# lighting_sign.net
KiCad netlist of a schematic drawn in EAGLE
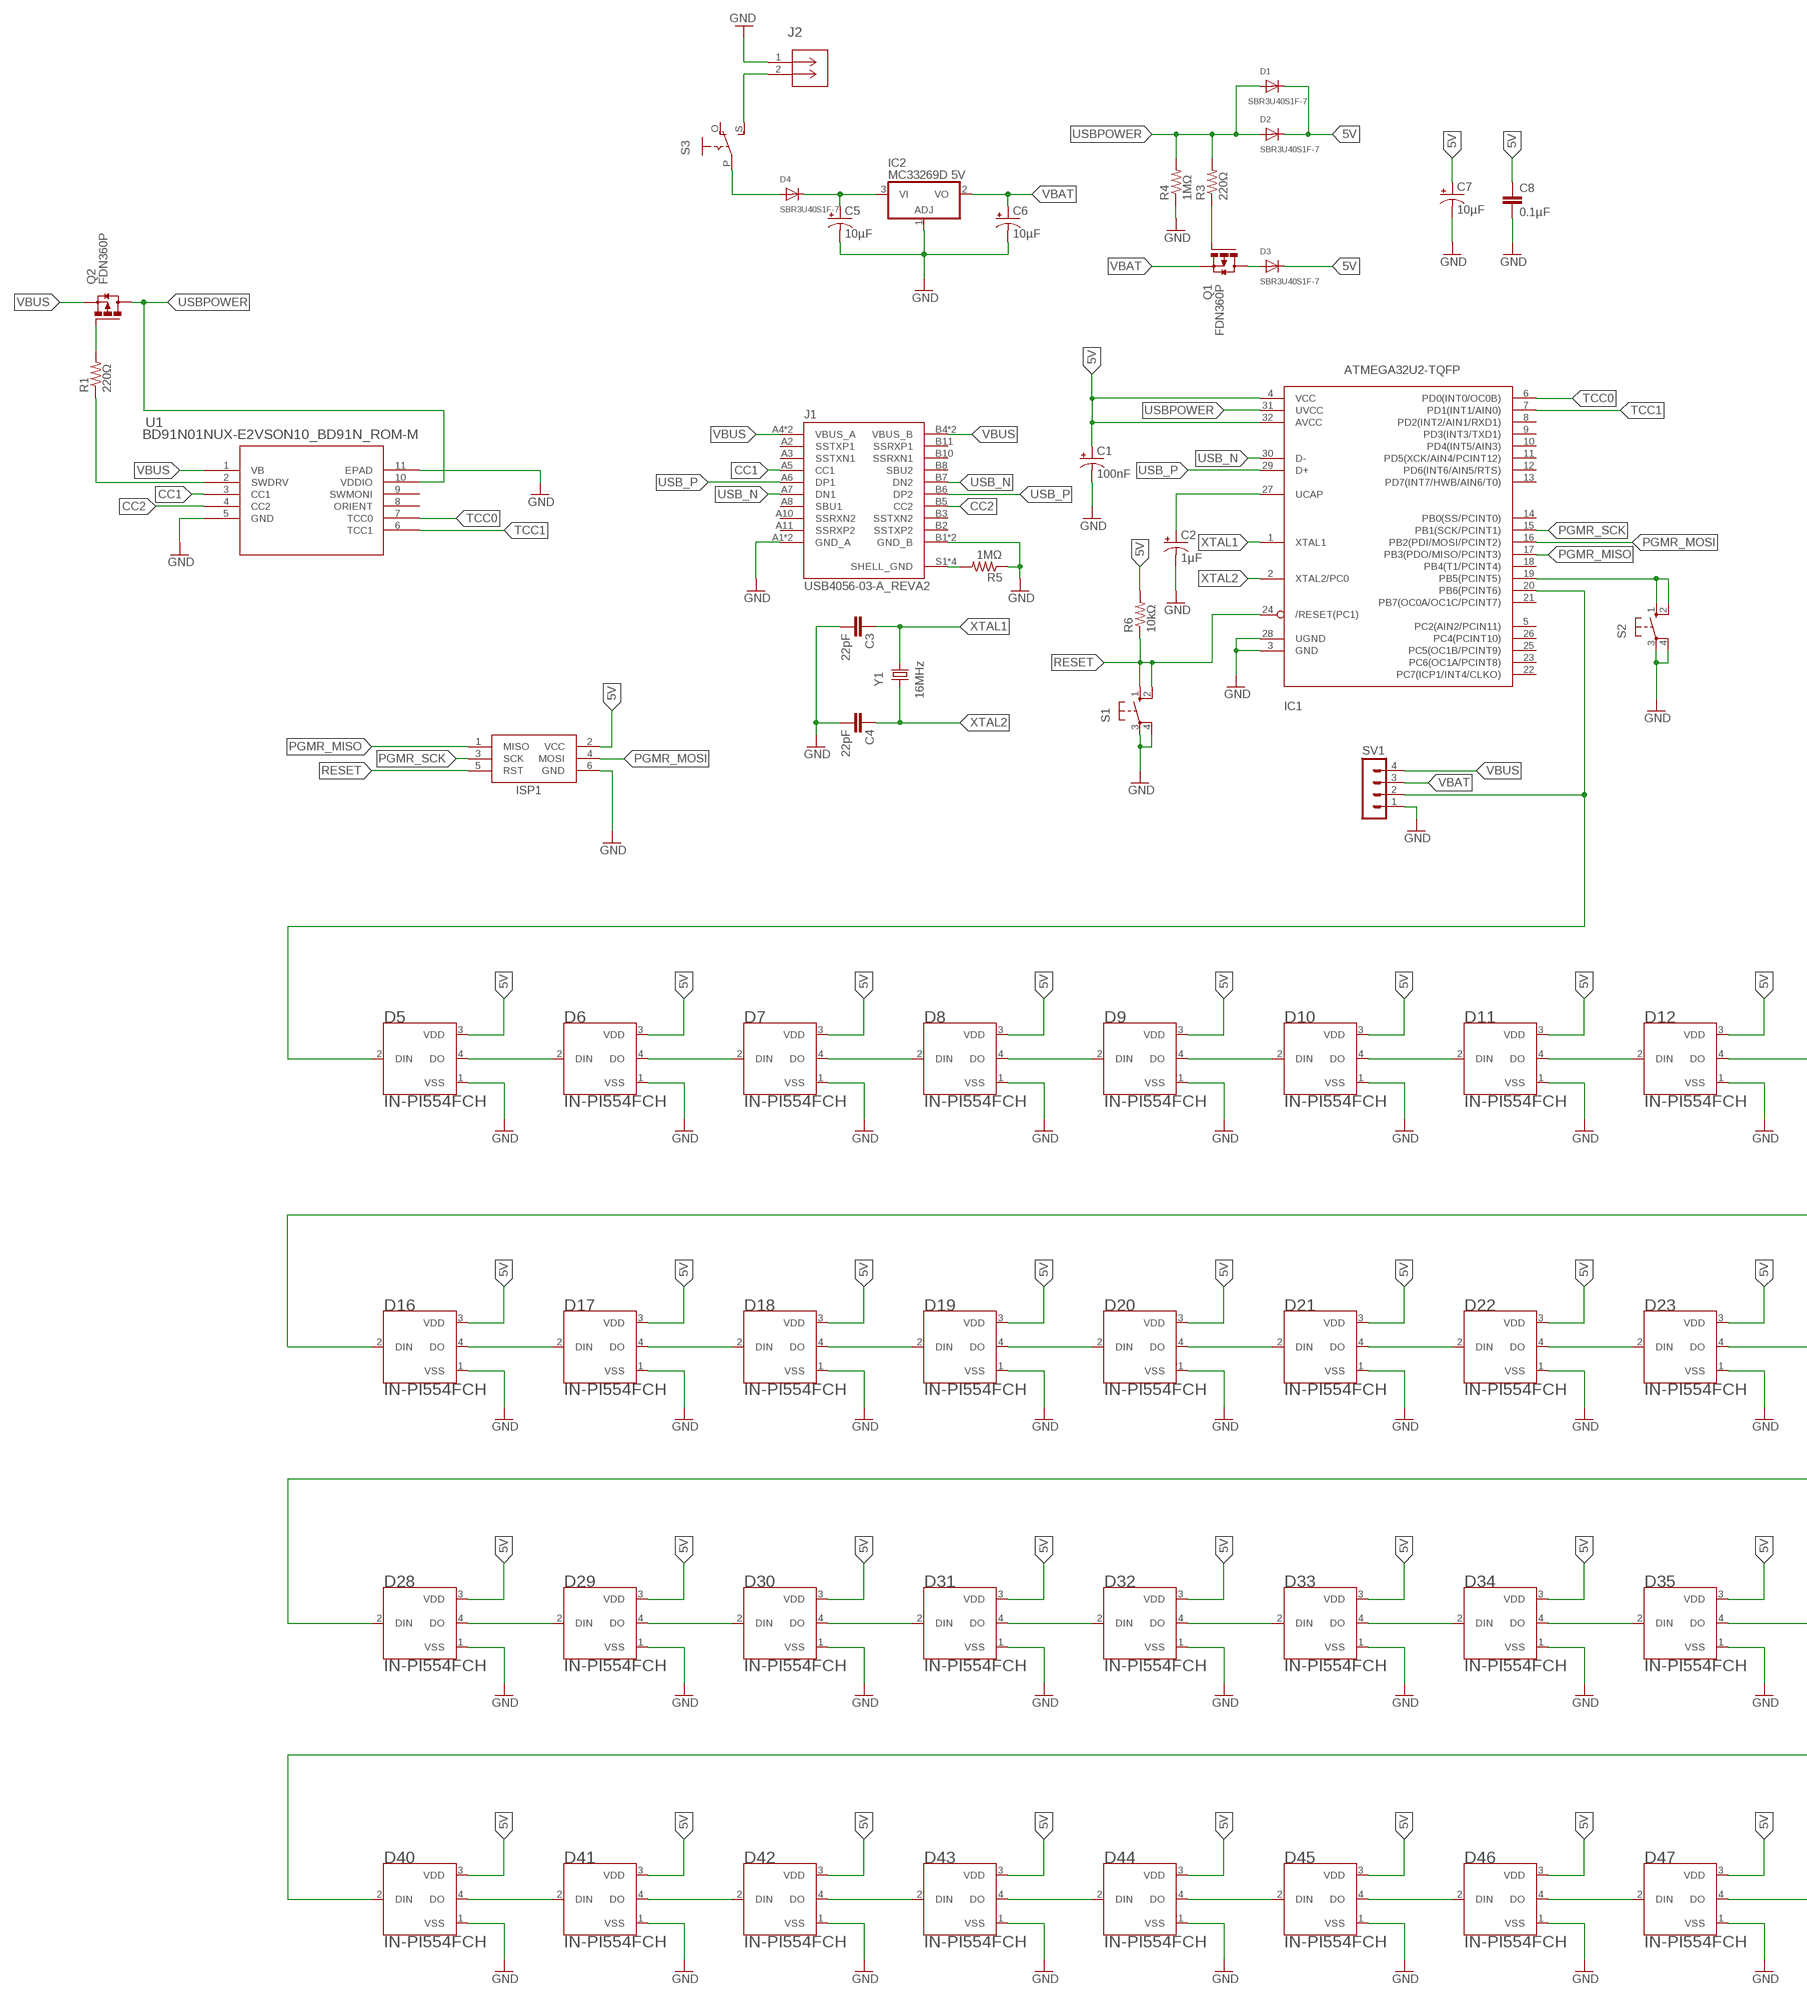
[diagram p0: schematic, sheet 1, part 1 of 2]
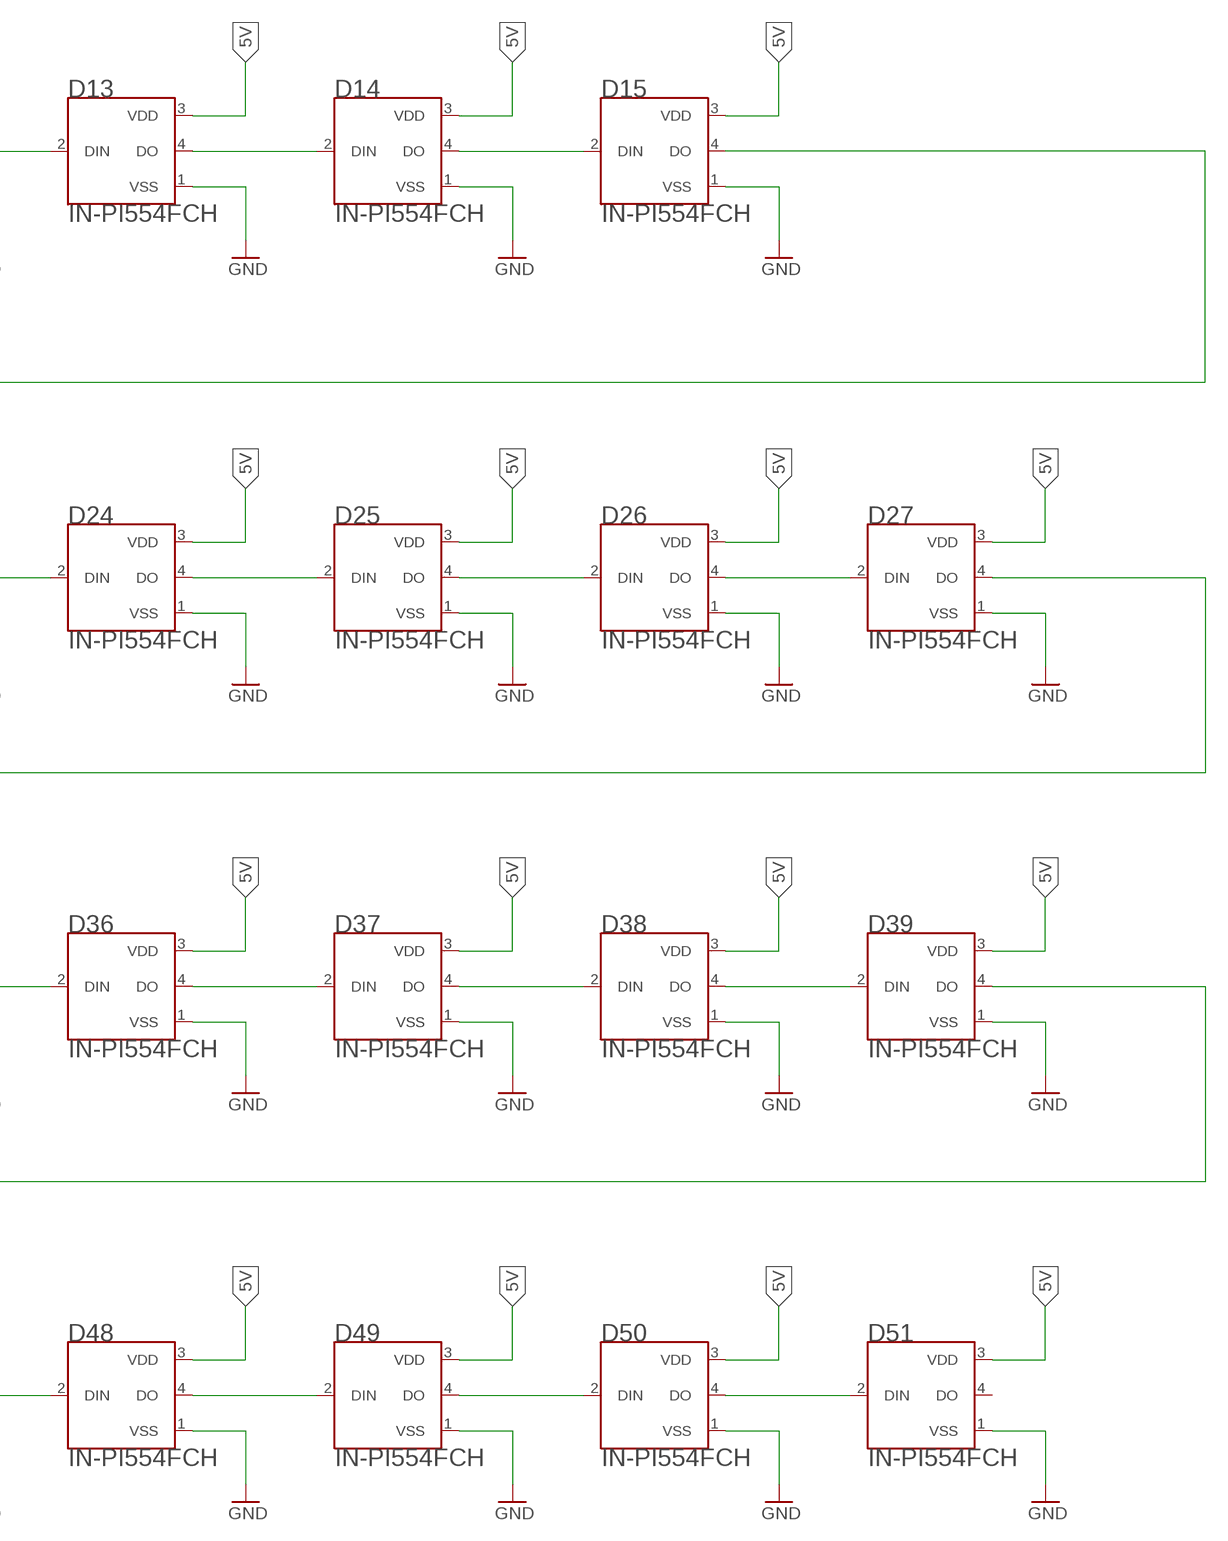
[diagram p1: schematic, sheet 1, part 2 of 2]

(export (version "E")
  (design (tool "Eeschema 10.0.6"))
  (components
    (comp (ref "C1")
      (value "100nF")
      (footprint "eagle-import:PANASONIC_B")
      (libsource (lib "eagle-import") (part "CPOL-USB"))
    )
    (comp (ref "C2")
      (value "1µF")
      (footprint "eagle-import:E2-5")
      (libsource (lib "eagle-import") (part "CPOL-USE2-5"))
    )
    (comp (ref "C3")
      (value "22pF")
      (footprint "eagle-import:C0402")
      (libsource (lib "eagle-import") (part "C-EUC0402"))
    )
    (comp (ref "C4")
      (value "22pF")
      (footprint "eagle-import:C0402")
      (libsource (lib "eagle-import") (part "C-EUC0402"))
    )
    (comp (ref "C5")
      (value "10µF")
      (footprint "eagle-import:PANASONIC_B")
      (libsource (lib "eagle-import") (part "CPOL-USB"))
    )
    (comp (ref "C6")
      (value "10µF")
      (footprint "eagle-import:PANASONIC_B")
      (libsource (lib "eagle-import") (part "CPOL-USB"))
    )
    (comp (ref "C7")
      (value "10µF")
      (footprint "eagle-import:PANASONIC_B")
      (libsource (lib "eagle-import") (part "CPOL-USB"))
    )
    (comp (ref "C8")
      (value "0.1µF")
      (footprint "eagle-import:C0402")
      (libsource (lib "eagle-import") (part "C-EUC0402"))
    )
    (comp (ref "D1")
      (value "SBR3U40S1F-7")
      (footprint "eagle-import:SOD-123")
      (libsource (lib "eagle-import") (part "DIODESOD-123"))
    )
    (comp (ref "D2")
      (value "SBR3U40S1F-7")
      (footprint "eagle-import:SOD-123")
      (libsource (lib "eagle-import") (part "DIODESOD-123"))
    )
    (comp (ref "D3")
      (value "SBR3U40S1F-7")
      (footprint "eagle-import:SOD-123")
      (libsource (lib "eagle-import") (part "DIODESOD-123"))
    )
    (comp (ref "D4")
      (value "SBR3U40S1F-7")
      (footprint "eagle-import:SOD-123")
      (libsource (lib "eagle-import") (part "DIODESOD-123"))
    )
    (comp (ref "D5")
      (value "IN-PI554FCH")
      (footprint "eagle-import:LED_IN-PI554FCH")
      (fields (field (name "MANUFACTURER") "Inolux"))
      (libsource (lib "eagle-import") (part "IN-PI554FCH"))
    )
    (comp (ref "D6")
      (value "IN-PI554FCH")
      (footprint "eagle-import:LED_IN-PI554FCH")
      (fields (field (name "MANUFACTURER") "Inolux"))
      (libsource (lib "eagle-import") (part "IN-PI554FCH"))
    )
    (comp (ref "D7")
      (value "IN-PI554FCH")
      (footprint "eagle-import:LED_IN-PI554FCH")
      (fields (field (name "MANUFACTURER") "Inolux"))
      (libsource (lib "eagle-import") (part "IN-PI554FCH"))
    )
    (comp (ref "D8")
      (value "IN-PI554FCH")
      (footprint "eagle-import:LED_IN-PI554FCH")
      (fields (field (name "MANUFACTURER") "Inolux"))
      (libsource (lib "eagle-import") (part "IN-PI554FCH"))
    )
    (comp (ref "D9")
      (value "IN-PI554FCH")
      (footprint "eagle-import:LED_IN-PI554FCH")
      (fields (field (name "MANUFACTURER") "Inolux"))
      (libsource (lib "eagle-import") (part "IN-PI554FCH"))
    )
    (comp (ref "D10")
      (value "IN-PI554FCH")
      (footprint "eagle-import:LED_IN-PI554FCH")
      (fields (field (name "MANUFACTURER") "Inolux"))
      (libsource (lib "eagle-import") (part "IN-PI554FCH"))
    )
    (comp (ref "D11")
      (value "IN-PI554FCH")
      (footprint "eagle-import:LED_IN-PI554FCH")
      (fields (field (name "MANUFACTURER") "Inolux"))
      (libsource (lib "eagle-import") (part "IN-PI554FCH"))
    )
    (comp (ref "D12")
      (value "IN-PI554FCH")
      (footprint "eagle-import:LED_IN-PI554FCH")
      (fields (field (name "MANUFACTURER") "Inolux"))
      (libsource (lib "eagle-import") (part "IN-PI554FCH"))
    )
    (comp (ref "D13")
      (value "IN-PI554FCH")
      (footprint "eagle-import:LED_IN-PI554FCH")
      (fields (field (name "MANUFACTURER") "Inolux"))
      (libsource (lib "eagle-import") (part "IN-PI554FCH"))
    )
    (comp (ref "D14")
      (value "IN-PI554FCH")
      (footprint "eagle-import:LED_IN-PI554FCH")
      (fields (field (name "MANUFACTURER") "Inolux"))
      (libsource (lib "eagle-import") (part "IN-PI554FCH"))
    )
    (comp (ref "D15")
      (value "IN-PI554FCH")
      (footprint "eagle-import:LED_IN-PI554FCH")
      (fields (field (name "MANUFACTURER") "Inolux"))
      (libsource (lib "eagle-import") (part "IN-PI554FCH"))
    )
    (comp (ref "D16")
      (value "IN-PI554FCH")
      (footprint "eagle-import:LED_IN-PI554FCH")
      (fields (field (name "MANUFACTURER") "Inolux"))
      (libsource (lib "eagle-import") (part "IN-PI554FCH"))
    )
    (comp (ref "D17")
      (value "IN-PI554FCH")
      (footprint "eagle-import:LED_IN-PI554FCH")
      (fields (field (name "MANUFACTURER") "Inolux"))
      (libsource (lib "eagle-import") (part "IN-PI554FCH"))
    )
    (comp (ref "D18")
      (value "IN-PI554FCH")
      (footprint "eagle-import:LED_IN-PI554FCH")
      (fields (field (name "MANUFACTURER") "Inolux"))
      (libsource (lib "eagle-import") (part "IN-PI554FCH"))
    )
    (comp (ref "D19")
      (value "IN-PI554FCH")
      (footprint "eagle-import:LED_IN-PI554FCH")
      (fields (field (name "MANUFACTURER") "Inolux"))
      (libsource (lib "eagle-import") (part "IN-PI554FCH"))
    )
    (comp (ref "D20")
      (value "IN-PI554FCH")
      (footprint "eagle-import:LED_IN-PI554FCH")
      (fields (field (name "MANUFACTURER") "Inolux"))
      (libsource (lib "eagle-import") (part "IN-PI554FCH"))
    )
    (comp (ref "D21")
      (value "IN-PI554FCH")
      (footprint "eagle-import:LED_IN-PI554FCH")
      (fields (field (name "MANUFACTURER") "Inolux"))
      (libsource (lib "eagle-import") (part "IN-PI554FCH"))
    )
    (comp (ref "D22")
      (value "IN-PI554FCH")
      (footprint "eagle-import:LED_IN-PI554FCH")
      (fields (field (name "MANUFACTURER") "Inolux"))
      (libsource (lib "eagle-import") (part "IN-PI554FCH"))
    )
    (comp (ref "D23")
      (value "IN-PI554FCH")
      (footprint "eagle-import:LED_IN-PI554FCH")
      (fields (field (name "MANUFACTURER") "Inolux"))
      (libsource (lib "eagle-import") (part "IN-PI554FCH"))
    )
    (comp (ref "D24")
      (value "IN-PI554FCH")
      (footprint "eagle-import:LED_IN-PI554FCH")
      (fields (field (name "MANUFACTURER") "Inolux"))
      (libsource (lib "eagle-import") (part "IN-PI554FCH"))
    )
    (comp (ref "D25")
      (value "IN-PI554FCH")
      (footprint "eagle-import:LED_IN-PI554FCH")
      (fields (field (name "MANUFACTURER") "Inolux"))
      (libsource (lib "eagle-import") (part "IN-PI554FCH"))
    )
    (comp (ref "D26")
      (value "IN-PI554FCH")
      (footprint "eagle-import:LED_IN-PI554FCH")
      (fields (field (name "MANUFACTURER") "Inolux"))
      (libsource (lib "eagle-import") (part "IN-PI554FCH"))
    )
    (comp (ref "D27")
      (value "IN-PI554FCH")
      (footprint "eagle-import:LED_IN-PI554FCH")
      (fields (field (name "MANUFACTURER") "Inolux"))
      (libsource (lib "eagle-import") (part "IN-PI554FCH"))
    )
    (comp (ref "D28")
      (value "IN-PI554FCH")
      (footprint "eagle-import:LED_IN-PI554FCH")
      (fields (field (name "MANUFACTURER") "Inolux"))
      (libsource (lib "eagle-import") (part "IN-PI554FCH"))
    )
    (comp (ref "D29")
      (value "IN-PI554FCH")
      (footprint "eagle-import:LED_IN-PI554FCH")
      (fields (field (name "MANUFACTURER") "Inolux"))
      (libsource (lib "eagle-import") (part "IN-PI554FCH"))
    )
    (comp (ref "D30")
      (value "IN-PI554FCH")
      (footprint "eagle-import:LED_IN-PI554FCH")
      (fields (field (name "MANUFACTURER") "Inolux"))
      (libsource (lib "eagle-import") (part "IN-PI554FCH"))
    )
    (comp (ref "D31")
      (value "IN-PI554FCH")
      (footprint "eagle-import:LED_IN-PI554FCH")
      (fields (field (name "MANUFACTURER") "Inolux"))
      (libsource (lib "eagle-import") (part "IN-PI554FCH"))
    )
    (comp (ref "D32")
      (value "IN-PI554FCH")
      (footprint "eagle-import:LED_IN-PI554FCH")
      (fields (field (name "MANUFACTURER") "Inolux"))
      (libsource (lib "eagle-import") (part "IN-PI554FCH"))
    )
    (comp (ref "D33")
      (value "IN-PI554FCH")
      (footprint "eagle-import:LED_IN-PI554FCH")
      (fields (field (name "MANUFACTURER") "Inolux"))
      (libsource (lib "eagle-import") (part "IN-PI554FCH"))
    )
    (comp (ref "D34")
      (value "IN-PI554FCH")
      (footprint "eagle-import:LED_IN-PI554FCH")
      (fields (field (name "MANUFACTURER") "Inolux"))
      (libsource (lib "eagle-import") (part "IN-PI554FCH"))
    )
    (comp (ref "D35")
      (value "IN-PI554FCH")
      (footprint "eagle-import:LED_IN-PI554FCH")
      (fields (field (name "MANUFACTURER") "Inolux"))
      (libsource (lib "eagle-import") (part "IN-PI554FCH"))
    )
    (comp (ref "D36")
      (value "IN-PI554FCH")
      (footprint "eagle-import:LED_IN-PI554FCH")
      (fields (field (name "MANUFACTURER") "Inolux"))
      (libsource (lib "eagle-import") (part "IN-PI554FCH"))
    )
    (comp (ref "D37")
      (value "IN-PI554FCH")
      (footprint "eagle-import:LED_IN-PI554FCH")
      (fields (field (name "MANUFACTURER") "Inolux"))
      (libsource (lib "eagle-import") (part "IN-PI554FCH"))
    )
    (comp (ref "D38")
      (value "IN-PI554FCH")
      (footprint "eagle-import:LED_IN-PI554FCH")
      (fields (field (name "MANUFACTURER") "Inolux"))
      (libsource (lib "eagle-import") (part "IN-PI554FCH"))
    )
    (comp (ref "D39")
      (value "IN-PI554FCH")
      (footprint "eagle-import:LED_IN-PI554FCH")
      (fields (field (name "MANUFACTURER") "Inolux"))
      (libsource (lib "eagle-import") (part "IN-PI554FCH"))
    )
    (comp (ref "D40")
      (value "IN-PI554FCH")
      (footprint "eagle-import:LED_IN-PI554FCH")
      (fields (field (name "MANUFACTURER") "Inolux"))
      (libsource (lib "eagle-import") (part "IN-PI554FCH"))
    )
    (comp (ref "D41")
      (value "IN-PI554FCH")
      (footprint "eagle-import:LED_IN-PI554FCH")
      (fields (field (name "MANUFACTURER") "Inolux"))
      (libsource (lib "eagle-import") (part "IN-PI554FCH"))
    )
    (comp (ref "D42")
      (value "IN-PI554FCH")
      (footprint "eagle-import:LED_IN-PI554FCH")
      (fields (field (name "MANUFACTURER") "Inolux"))
      (libsource (lib "eagle-import") (part "IN-PI554FCH"))
    )
    (comp (ref "D43")
      (value "IN-PI554FCH")
      (footprint "eagle-import:LED_IN-PI554FCH")
      (fields (field (name "MANUFACTURER") "Inolux"))
      (libsource (lib "eagle-import") (part "IN-PI554FCH"))
    )
    (comp (ref "D44")
      (value "IN-PI554FCH")
      (footprint "eagle-import:LED_IN-PI554FCH")
      (fields (field (name "MANUFACTURER") "Inolux"))
      (libsource (lib "eagle-import") (part "IN-PI554FCH"))
    )
    (comp (ref "D45")
      (value "IN-PI554FCH")
      (footprint "eagle-import:LED_IN-PI554FCH")
      (fields (field (name "MANUFACTURER") "Inolux"))
      (libsource (lib "eagle-import") (part "IN-PI554FCH"))
    )
    (comp (ref "D46")
      (value "IN-PI554FCH")
      (footprint "eagle-import:LED_IN-PI554FCH")
      (fields (field (name "MANUFACTURER") "Inolux"))
      (libsource (lib "eagle-import") (part "IN-PI554FCH"))
    )
    (comp (ref "D47")
      (value "IN-PI554FCH")
      (footprint "eagle-import:LED_IN-PI554FCH")
      (fields (field (name "MANUFACTURER") "Inolux"))
      (libsource (lib "eagle-import") (part "IN-PI554FCH"))
    )
    (comp (ref "D48")
      (value "IN-PI554FCH")
      (footprint "eagle-import:LED_IN-PI554FCH")
      (fields (field (name "MANUFACTURER") "Inolux"))
      (libsource (lib "eagle-import") (part "IN-PI554FCH"))
    )
    (comp (ref "D49")
      (value "IN-PI554FCH")
      (footprint "eagle-import:LED_IN-PI554FCH")
      (fields (field (name "MANUFACTURER") "Inolux"))
      (libsource (lib "eagle-import") (part "IN-PI554FCH"))
    )
    (comp (ref "D50")
      (value "IN-PI554FCH")
      (footprint "eagle-import:LED_IN-PI554FCH")
      (fields (field (name "MANUFACTURER") "Inolux"))
      (libsource (lib "eagle-import") (part "IN-PI554FCH"))
    )
    (comp (ref "D51")
      (value "IN-PI554FCH")
      (footprint "eagle-import:LED_IN-PI554FCH")
      (fields (field (name "MANUFACTURER") "Inolux"))
      (libsource (lib "eagle-import") (part "IN-PI554FCH"))
    )
    (comp (ref "IC1")
      (value "ATMEGA32U2-TQFP")
      (footprint "eagle-import:TQFP32-08")
      (libsource (lib "eagle-import") (part "ATMEGA32U2-TQFP"))
    )
    (comp (ref "IC2")
      (value "MC33269D 5V")
      (footprint "eagle-import:DPACK")
      (libsource (lib "eagle-import") (part "MC33269?D"))
    )
    (comp (ref "ISP1")
      (value "AVRISP-BOX")
      (footprint "eagle-import:AVRISP-BOX")
      (libsource (lib "eagle-import") (part "AVRISP-BOX"))
    )
    (comp (ref "J1")
      (value "USB4056-03-A_REVA2")
      (footprint "eagle-import:GCT_USB4056-03-A_REVA2")
      (fields (field (name "MANUFACTURER") "GCT"))
      (libsource (lib "eagle-import") (part "USB4056-03-A_REVA2"))
    )
    (comp (ref "J2")
      (value "BH9VPC 9V")
      (footprint "eagle-import:CONN_BH9VPC_MPD")
      (fields
        (field (name "MANUFACTURER_PART_NUMBER") "BH9VPC")
        (field (name "COPYRIGHT") "Copyright (C) 2024 Ultra Librarian. All rights reserved.")
      )
      (libsource (lib "eagle-import") (part "BH9VPC"))
    )
    (comp (ref "Q1")
      (value "FDN360P")
      (footprint "eagle-import:SUPER-SOT3")
      (libsource (lib "eagle-import") (part "FDN360P"))
    )
    (comp (ref "Q2")
      (value "FDN360P")
      (footprint "eagle-import:SUPER-SOT3")
      (libsource (lib "eagle-import") (part "FDN360P"))
    )
    (comp (ref "R1")
      (value "220Ω")
      (footprint "eagle-import:0207_10")
      (libsource (lib "eagle-import") (part "R-US_0207/10"))
    )
    (comp (ref "R3")
      (value "220Ω")
      (footprint "eagle-import:0207_10")
      (libsource (lib "eagle-import") (part "R-US_0207/10"))
    )
    (comp (ref "R4")
      (value "1MΩ")
      (footprint "eagle-import:0207_10")
      (libsource (lib "eagle-import") (part "R-US_0207/10"))
    )
    (comp (ref "R5")
      (value "1MΩ")
      (footprint "eagle-import:0207_10")
      (libsource (lib "eagle-import") (part "R-US_0207/10"))
    )
    (comp (ref "R6")
      (value "10kΩ")
      (footprint "eagle-import:0207_10")
      (libsource (lib "eagle-import") (part "R-US_0207/10"))
    )
    (comp (ref "S1")
      (value "10-XX")
      (footprint "eagle-import:B3F-10XX")
      (fields (field (name "MPN") "B3F-1000"))
      (libsource (lib "eagle-import") (part "10-XX"))
    )
    (comp (ref "S2")
      (value "10-XX")
      (footprint "eagle-import:B3F-10XX")
      (fields (field (name "MPN") "B3F-1000"))
      (libsource (lib "eagle-import") (part "10-XX"))
    )
    (comp (ref "S3")
      (value "EG1218S")
      (footprint "eagle-import:EG1218")
      (libsource (lib "eagle-import") (part "EG1218S"))
    )
    (comp (ref "SV1")
      (value "MA04-1")
      (footprint "eagle-import:MA04-1")
      (libsource (lib "eagle-import") (part "MA04-1"))
    )
    (comp (ref "U1")
      (value "BD91N01NUX-E2VSON10_BD91N_ROM-M")
      (footprint "eagle-import:VSON10_BD91N_ROM-M")
      (fields
        (field (name "MANUFACTURER_PART_NUMBER") "BD91N01NUX-E2")
        (field (name "COPYRIGHT") "Copyright (C) 2025 Ultra Librarian. All rights reserved.")
      )
      (libsource (lib "eagle-import") (part "BD91N01NUX-E2VSON10_BD91N_ROM-M"))
    )
    (comp (ref "Y1")
      (value "16MHz")
      (footprint "eagle-import:HC49U-V")
      (libsource (lib "eagle-import") (part "CRYSTALHC49U-V"))
    )
  )
  (nets
    (net (code "1") (name "5V") (class "Default")
      (node (ref "C1") (pin "+") (pinfunction "+_+") (pintype "passive"))
      (node (ref "C7") (pin "+") (pinfunction "+_+") (pintype "passive"))
      (node (ref "C8") (pin "1") (pinfunction "1_1") (pintype "passive"))
      (node (ref "D1") (pin "C") (pinfunction "C_C") (pintype "passive"))
      (node (ref "D10") (pin "3") (pinfunction "VDD_3") (pintype "power_in"))
      (node (ref "D11") (pin "3") (pinfunction "VDD_3") (pintype "power_in"))
      (node (ref "D12") (pin "3") (pinfunction "VDD_3") (pintype "power_in"))
      (node (ref "D13") (pin "3") (pinfunction "VDD_3") (pintype "power_in"))
      (node (ref "D14") (pin "3") (pinfunction "VDD_3") (pintype "power_in"))
      (node (ref "D15") (pin "3") (pinfunction "VDD_3") (pintype "power_in"))
      (node (ref "D16") (pin "3") (pinfunction "VDD_3") (pintype "power_in"))
      (node (ref "D17") (pin "3") (pinfunction "VDD_3") (pintype "power_in"))
      (node (ref "D18") (pin "3") (pinfunction "VDD_3") (pintype "power_in"))
      (node (ref "D19") (pin "3") (pinfunction "VDD_3") (pintype "power_in"))
      (node (ref "D2") (pin "C") (pinfunction "C_C") (pintype "passive"))
      (node (ref "D20") (pin "3") (pinfunction "VDD_3") (pintype "power_in"))
      (node (ref "D21") (pin "3") (pinfunction "VDD_3") (pintype "power_in"))
      (node (ref "D22") (pin "3") (pinfunction "VDD_3") (pintype "power_in"))
      (node (ref "D23") (pin "3") (pinfunction "VDD_3") (pintype "power_in"))
      (node (ref "D24") (pin "3") (pinfunction "VDD_3") (pintype "power_in"))
      (node (ref "D25") (pin "3") (pinfunction "VDD_3") (pintype "power_in"))
      (node (ref "D26") (pin "3") (pinfunction "VDD_3") (pintype "power_in"))
      (node (ref "D27") (pin "3") (pinfunction "VDD_3") (pintype "power_in"))
      (node (ref "D28") (pin "3") (pinfunction "VDD_3") (pintype "power_in"))
      (node (ref "D29") (pin "3") (pinfunction "VDD_3") (pintype "power_in"))
      (node (ref "D3") (pin "C") (pinfunction "C_C") (pintype "passive"))
      (node (ref "D30") (pin "3") (pinfunction "VDD_3") (pintype "power_in"))
      (node (ref "D31") (pin "3") (pinfunction "VDD_3") (pintype "power_in"))
      (node (ref "D32") (pin "3") (pinfunction "VDD_3") (pintype "power_in"))
      (node (ref "D33") (pin "3") (pinfunction "VDD_3") (pintype "power_in"))
      (node (ref "D34") (pin "3") (pinfunction "VDD_3") (pintype "power_in"))
      (node (ref "D35") (pin "3") (pinfunction "VDD_3") (pintype "power_in"))
      (node (ref "D36") (pin "3") (pinfunction "VDD_3") (pintype "power_in"))
      (node (ref "D37") (pin "3") (pinfunction "VDD_3") (pintype "power_in"))
      (node (ref "D38") (pin "3") (pinfunction "VDD_3") (pintype "power_in"))
      (node (ref "D39") (pin "3") (pinfunction "VDD_3") (pintype "power_in"))
      (node (ref "D40") (pin "3") (pinfunction "VDD_3") (pintype "power_in"))
      (node (ref "D41") (pin "3") (pinfunction "VDD_3") (pintype "power_in"))
      (node (ref "D42") (pin "3") (pinfunction "VDD_3") (pintype "power_in"))
      (node (ref "D43") (pin "3") (pinfunction "VDD_3") (pintype "power_in"))
      (node (ref "D44") (pin "3") (pinfunction "VDD_3") (pintype "power_in"))
      (node (ref "D45") (pin "3") (pinfunction "VDD_3") (pintype "power_in"))
      (node (ref "D46") (pin "3") (pinfunction "VDD_3") (pintype "power_in"))
      (node (ref "D47") (pin "3") (pinfunction "VDD_3") (pintype "power_in"))
      (node (ref "D48") (pin "3") (pinfunction "VDD_3") (pintype "power_in"))
      (node (ref "D49") (pin "3") (pinfunction "VDD_3") (pintype "power_in"))
      (node (ref "D5") (pin "3") (pinfunction "VDD_3") (pintype "power_in"))
      (node (ref "D50") (pin "3") (pinfunction "VDD_3") (pintype "power_in"))
      (node (ref "D51") (pin "3") (pinfunction "VDD_3") (pintype "power_in"))
      (node (ref "D6") (pin "3") (pinfunction "VDD_3") (pintype "power_in"))
      (node (ref "D7") (pin "3") (pinfunction "VDD_3") (pintype "power_in"))
      (node (ref "D8") (pin "3") (pinfunction "VDD_3") (pintype "power_in"))
      (node (ref "D9") (pin "3") (pinfunction "VDD_3") (pintype "power_in"))
      (node (ref "IC1") (pin "32") (pinfunction "AVCC_32") (pintype "bidirectional"))
      (node (ref "IC1") (pin "4") (pinfunction "VCC_4") (pintype "bidirectional"))
      (node (ref "ISP1") (pin "2") (pinfunction "VCC_2") (pintype "power_in"))
      (node (ref "R6") (pin "2") (pinfunction "2_2") (pintype "passive"))
    )
    (net (code "2") (name "CC1") (class "Default")
      (node (ref "J1") (pin "A5") (pinfunction "CC1_A5") (pintype "bidirectional"))
      (node (ref "U1") (pin "3") (pinfunction "CC1_3") (pintype "passive"))
    )
    (net (code "3") (name "CC2") (class "Default")
      (node (ref "J1") (pin "B5") (pinfunction "CC2_B5") (pintype "bidirectional"))
      (node (ref "U1") (pin "4") (pinfunction "CC2_4") (pintype "passive"))
    )
    (net (code "4") (name "GND") (class "Default")
      (node (ref "C1") (pin "-") (pinfunction "-_-") (pintype "passive"))
      (node (ref "C2") (pin "-") (pinfunction "-_-") (pintype "passive"))
      (node (ref "C3") (pin "2") (pinfunction "2_2") (pintype "passive"))
      (node (ref "C4") (pin "2") (pinfunction "2_2") (pintype "passive"))
      (node (ref "C5") (pin "-") (pinfunction "-_-") (pintype "passive"))
      (node (ref "C6") (pin "-") (pinfunction "-_-") (pintype "passive"))
      (node (ref "C7") (pin "-") (pinfunction "-_-") (pintype "passive"))
      (node (ref "C8") (pin "2") (pinfunction "2_2") (pintype "passive"))
      (node (ref "D10") (pin "1") (pinfunction "VSS_1") (pintype "power_in"))
      (node (ref "D11") (pin "1") (pinfunction "VSS_1") (pintype "power_in"))
      (node (ref "D12") (pin "1") (pinfunction "VSS_1") (pintype "power_in"))
      (node (ref "D13") (pin "1") (pinfunction "VSS_1") (pintype "power_in"))
      (node (ref "D14") (pin "1") (pinfunction "VSS_1") (pintype "power_in"))
      (node (ref "D15") (pin "1") (pinfunction "VSS_1") (pintype "power_in"))
      (node (ref "D16") (pin "1") (pinfunction "VSS_1") (pintype "power_in"))
      (node (ref "D17") (pin "1") (pinfunction "VSS_1") (pintype "power_in"))
      (node (ref "D18") (pin "1") (pinfunction "VSS_1") (pintype "power_in"))
      (node (ref "D19") (pin "1") (pinfunction "VSS_1") (pintype "power_in"))
      (node (ref "D20") (pin "1") (pinfunction "VSS_1") (pintype "power_in"))
      (node (ref "D21") (pin "1") (pinfunction "VSS_1") (pintype "power_in"))
      (node (ref "D22") (pin "1") (pinfunction "VSS_1") (pintype "power_in"))
      (node (ref "D23") (pin "1") (pinfunction "VSS_1") (pintype "power_in"))
      (node (ref "D24") (pin "1") (pinfunction "VSS_1") (pintype "power_in"))
      (node (ref "D25") (pin "1") (pinfunction "VSS_1") (pintype "power_in"))
      (node (ref "D26") (pin "1") (pinfunction "VSS_1") (pintype "power_in"))
      (node (ref "D27") (pin "1") (pinfunction "VSS_1") (pintype "power_in"))
      (node (ref "D28") (pin "1") (pinfunction "VSS_1") (pintype "power_in"))
      (node (ref "D29") (pin "1") (pinfunction "VSS_1") (pintype "power_in"))
      (node (ref "D30") (pin "1") (pinfunction "VSS_1") (pintype "power_in"))
      (node (ref "D31") (pin "1") (pinfunction "VSS_1") (pintype "power_in"))
      (node (ref "D32") (pin "1") (pinfunction "VSS_1") (pintype "power_in"))
      (node (ref "D33") (pin "1") (pinfunction "VSS_1") (pintype "power_in"))
      (node (ref "D34") (pin "1") (pinfunction "VSS_1") (pintype "power_in"))
      (node (ref "D35") (pin "1") (pinfunction "VSS_1") (pintype "power_in"))
      (node (ref "D36") (pin "1") (pinfunction "VSS_1") (pintype "power_in"))
      (node (ref "D37") (pin "1") (pinfunction "VSS_1") (pintype "power_in"))
      (node (ref "D38") (pin "1") (pinfunction "VSS_1") (pintype "power_in"))
      (node (ref "D39") (pin "1") (pinfunction "VSS_1") (pintype "power_in"))
      (node (ref "D40") (pin "1") (pinfunction "VSS_1") (pintype "power_in"))
      (node (ref "D41") (pin "1") (pinfunction "VSS_1") (pintype "power_in"))
      (node (ref "D42") (pin "1") (pinfunction "VSS_1") (pintype "power_in"))
      (node (ref "D43") (pin "1") (pinfunction "VSS_1") (pintype "power_in"))
      (node (ref "D44") (pin "1") (pinfunction "VSS_1") (pintype "power_in"))
      (node (ref "D45") (pin "1") (pinfunction "VSS_1") (pintype "power_in"))
      (node (ref "D46") (pin "1") (pinfunction "VSS_1") (pintype "power_in"))
      (node (ref "D47") (pin "1") (pinfunction "VSS_1") (pintype "power_in"))
      (node (ref "D48") (pin "1") (pinfunction "VSS_1") (pintype "power_in"))
      (node (ref "D49") (pin "1") (pinfunction "VSS_1") (pintype "power_in"))
      (node (ref "D5") (pin "1") (pinfunction "VSS_1") (pintype "power_in"))
      (node (ref "D50") (pin "1") (pinfunction "VSS_1") (pintype "power_in"))
      (node (ref "D51") (pin "1") (pinfunction "VSS_1") (pintype "power_in"))
      (node (ref "D6") (pin "1") (pinfunction "VSS_1") (pintype "power_in"))
      (node (ref "D7") (pin "1") (pinfunction "VSS_1") (pintype "power_in"))
      (node (ref "D8") (pin "1") (pinfunction "VSS_1") (pintype "power_in"))
      (node (ref "D9") (pin "1") (pinfunction "VSS_1") (pintype "power_in"))
      (node (ref "IC1") (pin "28") (pinfunction "UGND_28") (pintype "bidirectional"))
      (node (ref "IC1") (pin "3") (pinfunction "GND_3") (pintype "bidirectional"))
      (node (ref "IC2") (pin "1") (pinfunction "ADJ_1") (pintype "input"))
      (node (ref "ISP1") (pin "6") (pinfunction "GND_6") (pintype "power_in"))
      (node (ref "J1") (pin "A1") (pinfunction "GND_A_A1") (pintype "power_in"))
      (node (ref "J1") (pin "A12") (pinfunction "GND_A_A12") (pintype "power_in"))
      (node (ref "J1") (pin "B1") (pinfunction "GND_B_B1") (pintype "power_in"))
      (node (ref "J1") (pin "B12") (pinfunction "GND_B_B12") (pintype "power_in"))
      (node (ref "J2") (pin "1") (pinfunction "1_1") (pintype "passive"))
      (node (ref "R4") (pin "1") (pinfunction "1_1") (pintype "passive"))
      (node (ref "R5") (pin "1") (pinfunction "1_1") (pintype "passive"))
      (node (ref "S1") (pin "3") (pinfunction "P_3") (pintype "passive"))
      (node (ref "S1") (pin "4") (pinfunction "P1_4") (pintype "passive"))
      (node (ref "S2") (pin "3") (pinfunction "P_3") (pintype "passive"))
      (node (ref "S2") (pin "4") (pinfunction "P1_4") (pintype "passive"))
      (node (ref "SV1") (pin "1") (pinfunction "1_1") (pintype "passive"))
      (node (ref "U1") (pin "11") (pinfunction "EPAD_11") (pintype "passive"))
      (node (ref "U1") (pin "5") (pinfunction "GND_5") (pintype "passive"))
    )
    (net (code "5") (name "Net-(D4-PadA)") (class "Default")
      (node (ref "D4") (pin "A") (pinfunction "A_A") (pintype "passive"))
      (node (ref "S3") (pin "P") (pinfunction "P_P") (pintype "passive"))
    )
    (net (code "6") (name "Net-(D5-DIN)") (class "Default")
      (node (ref "D5") (pin "2") (pinfunction "DIN_2") (pintype "input"))
      (node (ref "IC1") (pin "20") (pinfunction "PB6(PCINT6)_20") (pintype "bidirectional"))
      (node (ref "SV1") (pin "2") (pinfunction "2_2") (pintype "passive"))
    )
    (net (code "7") (name "Net-(D5-DO)") (class "Default")
      (node (ref "D5") (pin "4") (pinfunction "DO_4") (pintype "output"))
      (node (ref "D6") (pin "2") (pinfunction "DIN_2") (pintype "input"))
    )
    (net (code "8") (name "Net-(D6-DO)") (class "Default")
      (node (ref "D6") (pin "4") (pinfunction "DO_4") (pintype "output"))
      (node (ref "D7") (pin "2") (pinfunction "DIN_2") (pintype "input"))
    )
    (net (code "9") (name "Net-(D7-DO)") (class "Default")
      (node (ref "D7") (pin "4") (pinfunction "DO_4") (pintype "output"))
      (node (ref "D8") (pin "2") (pinfunction "DIN_2") (pintype "input"))
    )
    (net (code "10") (name "Net-(D8-DO)") (class "Default")
      (node (ref "D8") (pin "4") (pinfunction "DO_4") (pintype "output"))
      (node (ref "D9") (pin "2") (pinfunction "DIN_2") (pintype "input"))
    )
    (net (code "11") (name "Net-(D10-DIN)") (class "Default")
      (node (ref "D10") (pin "2") (pinfunction "DIN_2") (pintype "input"))
      (node (ref "D9") (pin "4") (pinfunction "DO_4") (pintype "output"))
    )
    (net (code "12") (name "Net-(D10-DO)") (class "Default")
      (node (ref "D10") (pin "4") (pinfunction "DO_4") (pintype "output"))
      (node (ref "D11") (pin "2") (pinfunction "DIN_2") (pintype "input"))
    )
    (net (code "13") (name "Net-(D11-DO)") (class "Default")
      (node (ref "D11") (pin "4") (pinfunction "DO_4") (pintype "output"))
      (node (ref "D12") (pin "2") (pinfunction "DIN_2") (pintype "input"))
    )
    (net (code "14") (name "Net-(D12-DO)") (class "Default")
      (node (ref "D12") (pin "4") (pinfunction "DO_4") (pintype "output"))
      (node (ref "D13") (pin "2") (pinfunction "DIN_2") (pintype "input"))
    )
    (net (code "15") (name "Net-(D13-DO)") (class "Default")
      (node (ref "D13") (pin "4") (pinfunction "DO_4") (pintype "output"))
      (node (ref "D14") (pin "2") (pinfunction "DIN_2") (pintype "input"))
    )
    (net (code "16") (name "Net-(D14-DO)") (class "Default")
      (node (ref "D14") (pin "4") (pinfunction "DO_4") (pintype "output"))
      (node (ref "D15") (pin "2") (pinfunction "DIN_2") (pintype "input"))
    )
    (net (code "17") (name "Net-(D15-DO)") (class "Default")
      (node (ref "D15") (pin "4") (pinfunction "DO_4") (pintype "output"))
      (node (ref "D16") (pin "2") (pinfunction "DIN_2") (pintype "input"))
    )
    (net (code "18") (name "Net-(D16-DO)") (class "Default")
      (node (ref "D16") (pin "4") (pinfunction "DO_4") (pintype "output"))
      (node (ref "D17") (pin "2") (pinfunction "DIN_2") (pintype "input"))
    )
    (net (code "19") (name "Net-(D17-DO)") (class "Default")
      (node (ref "D17") (pin "4") (pinfunction "DO_4") (pintype "output"))
      (node (ref "D18") (pin "2") (pinfunction "DIN_2") (pintype "input"))
    )
    (net (code "20") (name "Net-(D18-DO)") (class "Default")
      (node (ref "D18") (pin "4") (pinfunction "DO_4") (pintype "output"))
      (node (ref "D19") (pin "2") (pinfunction "DIN_2") (pintype "input"))
    )
    (net (code "21") (name "Net-(D19-DO)") (class "Default")
      (node (ref "D19") (pin "4") (pinfunction "DO_4") (pintype "output"))
      (node (ref "D20") (pin "2") (pinfunction "DIN_2") (pintype "input"))
    )
    (net (code "22") (name "Net-(D20-DO)") (class "Default")
      (node (ref "D20") (pin "4") (pinfunction "DO_4") (pintype "output"))
      (node (ref "D21") (pin "2") (pinfunction "DIN_2") (pintype "input"))
    )
    (net (code "23") (name "Net-(D21-DO)") (class "Default")
      (node (ref "D21") (pin "4") (pinfunction "DO_4") (pintype "output"))
      (node (ref "D22") (pin "2") (pinfunction "DIN_2") (pintype "input"))
    )
    (net (code "24") (name "Net-(D22-DO)") (class "Default")
      (node (ref "D22") (pin "4") (pinfunction "DO_4") (pintype "output"))
      (node (ref "D23") (pin "2") (pinfunction "DIN_2") (pintype "input"))
    )
    (net (code "25") (name "Net-(D23-DO)") (class "Default")
      (node (ref "D23") (pin "4") (pinfunction "DO_4") (pintype "output"))
      (node (ref "D24") (pin "2") (pinfunction "DIN_2") (pintype "input"))
    )
    (net (code "26") (name "Net-(D24-DO)") (class "Default")
      (node (ref "D24") (pin "4") (pinfunction "DO_4") (pintype "output"))
      (node (ref "D25") (pin "2") (pinfunction "DIN_2") (pintype "input"))
    )
    (net (code "27") (name "Net-(D25-DO)") (class "Default")
      (node (ref "D25") (pin "4") (pinfunction "DO_4") (pintype "output"))
      (node (ref "D26") (pin "2") (pinfunction "DIN_2") (pintype "input"))
    )
    (net (code "28") (name "Net-(D26-DO)") (class "Default")
      (node (ref "D26") (pin "4") (pinfunction "DO_4") (pintype "output"))
      (node (ref "D27") (pin "2") (pinfunction "DIN_2") (pintype "input"))
    )
    (net (code "29") (name "Net-(D27-DO)") (class "Default")
      (node (ref "D27") (pin "4") (pinfunction "DO_4") (pintype "output"))
      (node (ref "D28") (pin "2") (pinfunction "DIN_2") (pintype "input"))
    )
    (net (code "30") (name "Net-(D28-DO)") (class "Default")
      (node (ref "D28") (pin "4") (pinfunction "DO_4") (pintype "output"))
      (node (ref "D29") (pin "2") (pinfunction "DIN_2") (pintype "input"))
    )
    (net (code "31") (name "Net-(D29-DO)") (class "Default")
      (node (ref "D29") (pin "4") (pinfunction "DO_4") (pintype "output"))
      (node (ref "D30") (pin "2") (pinfunction "DIN_2") (pintype "input"))
    )
    (net (code "32") (name "Net-(D30-DO)") (class "Default")
      (node (ref "D30") (pin "4") (pinfunction "DO_4") (pintype "output"))
      (node (ref "D31") (pin "2") (pinfunction "DIN_2") (pintype "input"))
    )
    (net (code "33") (name "Net-(D31-DO)") (class "Default")
      (node (ref "D31") (pin "4") (pinfunction "DO_4") (pintype "output"))
      (node (ref "D32") (pin "2") (pinfunction "DIN_2") (pintype "input"))
    )
    (net (code "34") (name "Net-(D32-DO)") (class "Default")
      (node (ref "D32") (pin "4") (pinfunction "DO_4") (pintype "output"))
      (node (ref "D33") (pin "2") (pinfunction "DIN_2") (pintype "input"))
    )
    (net (code "35") (name "Net-(D33-DO)") (class "Default")
      (node (ref "D33") (pin "4") (pinfunction "DO_4") (pintype "output"))
      (node (ref "D34") (pin "2") (pinfunction "DIN_2") (pintype "input"))
    )
    (net (code "36") (name "Net-(D34-DO)") (class "Default")
      (node (ref "D34") (pin "4") (pinfunction "DO_4") (pintype "output"))
      (node (ref "D35") (pin "2") (pinfunction "DIN_2") (pintype "input"))
    )
    (net (code "37") (name "Net-(D35-DO)") (class "Default")
      (node (ref "D35") (pin "4") (pinfunction "DO_4") (pintype "output"))
      (node (ref "D36") (pin "2") (pinfunction "DIN_2") (pintype "input"))
    )
    (net (code "38") (name "Net-(D36-DO)") (class "Default")
      (node (ref "D36") (pin "4") (pinfunction "DO_4") (pintype "output"))
      (node (ref "D37") (pin "2") (pinfunction "DIN_2") (pintype "input"))
    )
    (net (code "39") (name "Net-(D37-DO)") (class "Default")
      (node (ref "D37") (pin "4") (pinfunction "DO_4") (pintype "output"))
      (node (ref "D38") (pin "2") (pinfunction "DIN_2") (pintype "input"))
    )
    (net (code "40") (name "Net-(D38-DO)") (class "Default")
      (node (ref "D38") (pin "4") (pinfunction "DO_4") (pintype "output"))
      (node (ref "D39") (pin "2") (pinfunction "DIN_2") (pintype "input"))
    )
    (net (code "41") (name "Net-(D39-DO)") (class "Default")
      (node (ref "D39") (pin "4") (pinfunction "DO_4") (pintype "output"))
      (node (ref "D40") (pin "2") (pinfunction "DIN_2") (pintype "input"))
    )
    (net (code "42") (name "Net-(D40-DO)") (class "Default")
      (node (ref "D40") (pin "4") (pinfunction "DO_4") (pintype "output"))
      (node (ref "D41") (pin "2") (pinfunction "DIN_2") (pintype "input"))
    )
    (net (code "43") (name "Net-(D41-DO)") (class "Default")
      (node (ref "D41") (pin "4") (pinfunction "DO_4") (pintype "output"))
      (node (ref "D42") (pin "2") (pinfunction "DIN_2") (pintype "input"))
    )
    (net (code "44") (name "Net-(D42-DO)") (class "Default")
      (node (ref "D42") (pin "4") (pinfunction "DO_4") (pintype "output"))
      (node (ref "D43") (pin "2") (pinfunction "DIN_2") (pintype "input"))
    )
    (net (code "45") (name "Net-(D43-DO)") (class "Default")
      (node (ref "D43") (pin "4") (pinfunction "DO_4") (pintype "output"))
      (node (ref "D44") (pin "2") (pinfunction "DIN_2") (pintype "input"))
    )
    (net (code "46") (name "Net-(D44-DO)") (class "Default")
      (node (ref "D44") (pin "4") (pinfunction "DO_4") (pintype "output"))
      (node (ref "D45") (pin "2") (pinfunction "DIN_2") (pintype "input"))
    )
    (net (code "47") (name "Net-(D45-DO)") (class "Default")
      (node (ref "D45") (pin "4") (pinfunction "DO_4") (pintype "output"))
      (node (ref "D46") (pin "2") (pinfunction "DIN_2") (pintype "input"))
    )
    (net (code "48") (name "Net-(D46-DO)") (class "Default")
      (node (ref "D46") (pin "4") (pinfunction "DO_4") (pintype "output"))
      (node (ref "D47") (pin "2") (pinfunction "DIN_2") (pintype "input"))
    )
    (net (code "49") (name "Net-(D47-DO)") (class "Default")
      (node (ref "D47") (pin "4") (pinfunction "DO_4") (pintype "output"))
      (node (ref "D48") (pin "2") (pinfunction "DIN_2") (pintype "input"))
    )
    (net (code "50") (name "Net-(D48-DO)") (class "Default")
      (node (ref "D48") (pin "4") (pinfunction "DO_4") (pintype "output"))
      (node (ref "D49") (pin "2") (pinfunction "DIN_2") (pintype "input"))
    )
    (net (code "51") (name "Net-(D49-DO)") (class "Default")
      (node (ref "D49") (pin "4") (pinfunction "DO_4") (pintype "output"))
      (node (ref "D50") (pin "2") (pinfunction "DIN_2") (pintype "input"))
    )
    (net (code "52") (name "Net-(D50-DO)") (class "Default")
      (node (ref "D50") (pin "4") (pinfunction "DO_4") (pintype "output"))
      (node (ref "D51") (pin "2") (pinfunction "DIN_2") (pintype "input"))
    )
    (net (code "53") (name "Net-(IC1-PB5(PCINT5))") (class "Default")
      (node (ref "IC1") (pin "19") (pinfunction "PB5(PCINT5)_19") (pintype "bidirectional"))
      (node (ref "S2") (pin "1") (pinfunction "S_1") (pintype "passive"))
      (node (ref "S2") (pin "2") (pinfunction "S1_2") (pintype "passive"))
    )
    (net (code "54") (name "Net-(IC1-UCAP)") (class "Default")
      (node (ref "C2") (pin "+") (pinfunction "+_+") (pintype "passive"))
      (node (ref "IC1") (pin "27") (pinfunction "UCAP_27") (pintype "bidirectional"))
    )
    (net (code "55") (name "Net-(IC2-VI)") (class "Default")
      (node (ref "C5") (pin "+") (pinfunction "+_+") (pintype "passive"))
      (node (ref "D4") (pin "C") (pinfunction "C_C") (pintype "passive"))
      (node (ref "IC2") (pin "3") (pinfunction "VI_3") (pintype "input"))
    )
    (net (code "56") (name "Net-(J1-SHELL_GND-PadS1)") (class "Default")
      (node (ref "J1") (pin "S1") (pinfunction "SHELL_GND_S1") (pintype "power_in"))
      (node (ref "J1") (pin "S2") (pinfunction "SHELL_GND_S2") (pintype "power_in"))
      (node (ref "J1") (pin "S3") (pinfunction "SHELL_GND_S3") (pintype "power_in"))
      (node (ref "J1") (pin "S4") (pinfunction "SHELL_GND_S4") (pintype "power_in"))
      (node (ref "R5") (pin "2") (pinfunction "2_2") (pintype "passive"))
    )
    (net (code "57") (name "Net-(J2-Pad2)") (class "Default")
      (node (ref "J2") (pin "2") (pinfunction "2_2") (pintype "passive"))
      (node (ref "S3") (pin "S") (pinfunction "S_S") (pintype "passive"))
    )
    (net (code "58") (name "Net-(Q1-D)") (class "Default")
      (node (ref "D3") (pin "A") (pinfunction "A_A") (pintype "passive"))
      (node (ref "Q1") (pin "3") (pinfunction "D_3") (pintype "passive"))
    )
    (net (code "59") (name "Net-(Q1-G)") (class "Default")
      (node (ref "Q1") (pin "1") (pinfunction "G_1") (pintype "passive"))
      (node (ref "R3") (pin "1") (pinfunction "1_1") (pintype "passive"))
    )
    (net (code "60") (name "Net-(Q2-G)") (class "Default")
      (node (ref "Q2") (pin "1") (pinfunction "G_1") (pintype "passive"))
      (node (ref "R1") (pin "2") (pinfunction "2_2") (pintype "passive"))
    )
    (net (code "61") (name "Net-(U1-SWDRV)") (class "Default")
      (node (ref "R1") (pin "1") (pinfunction "1_1") (pintype "passive"))
      (node (ref "U1") (pin "2") (pinfunction "SWDRV_2") (pintype "output"))
    )
    (net (code "62") (name "PGMR_MISO") (class "Default")
      (node (ref "IC1") (pin "17") (pinfunction "PB3(PDO/MISO/PCINT3)_17") (pintype "bidirectional"))
      (node (ref "ISP1") (pin "1") (pinfunction "MISO_1") (pintype "input"))
    )
    (net (code "63") (name "PGMR_MOSI") (class "Default")
      (node (ref "IC1") (pin "16") (pinfunction "PB2(PDI/MOSI/PCINT2)_16") (pintype "bidirectional"))
      (node (ref "ISP1") (pin "4") (pinfunction "MOSI_4") (pintype "output"))
    )
    (net (code "64") (name "PGMR_SCK") (class "Default")
      (node (ref "IC1") (pin "15") (pinfunction "PB1(SCK/PCINT1)_15") (pintype "bidirectional"))
      (node (ref "ISP1") (pin "3") (pinfunction "SCK_3") (pintype "output"))
    )
    (net (code "65") (name "RESET") (class "Default")
      (node (ref "IC1") (pin "24") (pinfunction "/RESET(PC1)_24") (pintype "bidirectional"))
      (node (ref "ISP1") (pin "5") (pinfunction "RST_5") (pintype "output"))
      (node (ref "R6") (pin "1") (pinfunction "1_1") (pintype "passive"))
      (node (ref "S1") (pin "1") (pinfunction "S_1") (pintype "passive"))
      (node (ref "S1") (pin "2") (pinfunction "S1_2") (pintype "passive"))
    )
    (net (code "66") (name "TCC0") (class "Default")
      (node (ref "IC1") (pin "6") (pinfunction "PD0(INT0/OC0B)_6") (pintype "bidirectional"))
      (node (ref "U1") (pin "7") (pinfunction "TCC0_7") (pintype "passive"))
    )
    (net (code "67") (name "TCC1") (class "Default")
      (node (ref "IC1") (pin "7") (pinfunction "PD1(INT1/AIN0)_7") (pintype "bidirectional"))
      (node (ref "U1") (pin "6") (pinfunction "TCC1_6") (pintype "passive"))
    )
    (net (code "68") (name "USBPOWER") (class "Default")
      (node (ref "D1") (pin "A") (pinfunction "A_A") (pintype "passive"))
      (node (ref "D2") (pin "A") (pinfunction "A_A") (pintype "passive"))
      (node (ref "IC1") (pin "31") (pinfunction "UVCC_31") (pintype "bidirectional"))
      (node (ref "Q2") (pin "3") (pinfunction "D_3") (pintype "passive"))
      (node (ref "R3") (pin "2") (pinfunction "2_2") (pintype "passive"))
      (node (ref "R4") (pin "2") (pinfunction "2_2") (pintype "passive"))
      (node (ref "U1") (pin "10") (pinfunction "VDDIO_10") (pintype "power_in"))
    )
    (net (code "69") (name "USB_N") (class "Default")
      (node (ref "IC1") (pin "30") (pinfunction "D-_30") (pintype "bidirectional"))
      (node (ref "J1") (pin "A7") (pinfunction "DN1_A7") (pintype "bidirectional"))
      (node (ref "J1") (pin "B7") (pinfunction "DN2_B7") (pintype "bidirectional"))
    )
    (net (code "70") (name "USB_P") (class "Default")
      (node (ref "IC1") (pin "29") (pinfunction "D+_29") (pintype "bidirectional"))
      (node (ref "J1") (pin "A6") (pinfunction "DP1_A6") (pintype "bidirectional"))
      (node (ref "J1") (pin "B6") (pinfunction "DP2_B6") (pintype "bidirectional"))
    )
    (net (code "71") (name "VBAT") (class "Default")
      (node (ref "C6") (pin "+") (pinfunction "+_+") (pintype "passive"))
      (node (ref "IC2") (pin "2") (pinfunction "VO_2") (pintype "passive"))
      (node (ref "Q1") (pin "2") (pinfunction "S_2") (pintype "passive"))
      (node (ref "SV1") (pin "3") (pinfunction "3_3") (pintype "passive"))
    )
    (net (code "72") (name "VBUS") (class "Default")
      (node (ref "J1") (pin "A4") (pinfunction "VBUS_A_A4") (pintype "power_in"))
      (node (ref "J1") (pin "A9") (pinfunction "VBUS_A_A9") (pintype "power_in"))
      (node (ref "J1") (pin "B4") (pinfunction "VBUS_B_B4") (pintype "power_in"))
      (node (ref "J1") (pin "B9") (pinfunction "VBUS_B_B9") (pintype "power_in"))
      (node (ref "Q2") (pin "2") (pinfunction "S_2") (pintype "passive"))
      (node (ref "SV1") (pin "4") (pinfunction "4_4") (pintype "passive"))
      (node (ref "U1") (pin "1") (pinfunction "VB_1") (pintype "power_in"))
    )
    (net (code "73") (name "XTAL1") (class "Default")
      (node (ref "C3") (pin "1") (pinfunction "1_1") (pintype "passive"))
      (node (ref "IC1") (pin "1") (pinfunction "XTAL1_1") (pintype "bidirectional"))
      (node (ref "Y1") (pin "2") (pinfunction "2_2") (pintype "passive"))
    )
    (net (code "74") (name "XTAL2") (class "Default")
      (node (ref "C4") (pin "1") (pinfunction "1_1") (pintype "passive"))
      (node (ref "IC1") (pin "2") (pinfunction "XTAL2/PC0_2") (pintype "bidirectional"))
      (node (ref "Y1") (pin "1") (pinfunction "1_1") (pintype "passive"))
    )
    (net (code "75") (name "unconnected-(D51-DO-Pad4)") (class "Default")
      (node (ref "D51") (pin "4") (pinfunction "DO_4") (pintype "output"))
    )
    (net (code "76") (name "unconnected-(IC1-PB0(SS{slash}PCINT0)-Pad14)") (class "Default")
      (node (ref "IC1") (pin "14") (pinfunction "PB0(SS/PCINT0)_14") (pintype "bidirectional"))
    )
    (net (code "77") (name "unconnected-(IC1-PB4(T1{slash}PCINT4)-Pad18)") (class "Default")
      (node (ref "IC1") (pin "18") (pinfunction "PB4(T1/PCINT4)_18") (pintype "bidirectional"))
    )
    (net (code "78") (name "unconnected-(IC1-PB7(OC0A{slash}OC1C{slash}PCINT7)-Pad21)") (class "Default")
      (node (ref "IC1") (pin "21") (pinfunction "PB7(OC0A/OC1C/PCINT7)_21") (pintype "bidirectional"))
    )
    (net (code "79") (name "unconnected-(IC1-PC2(AIN2{slash}PCIN11)-Pad5)") (class "Default")
      (node (ref "IC1") (pin "5") (pinfunction "PC2(AIN2/PCIN11)_5") (pintype "bidirectional"))
    )
    (net (code "80") (name "unconnected-(IC1-PC4(PCINT10)-Pad26)") (class "Default")
      (node (ref "IC1") (pin "26") (pinfunction "PC4(PCINT10)_26") (pintype "bidirectional"))
    )
    (net (code "81") (name "unconnected-(IC1-PC5(OC1B{slash}PCINT9)-Pad25)") (class "Default")
      (node (ref "IC1") (pin "25") (pinfunction "PC5(OC1B/PCINT9)_25") (pintype "bidirectional"))
    )
    (net (code "82") (name "unconnected-(IC1-PC6(OC1A{slash}PCINT8)-Pad23)") (class "Default")
      (node (ref "IC1") (pin "23") (pinfunction "PC6(OC1A/PCINT8)_23") (pintype "bidirectional"))
    )
    (net (code "83") (name "unconnected-(IC1-PC7(ICP1{slash}INT4{slash}CLKO)-Pad22)") (class "Default")
      (node (ref "IC1") (pin "22") (pinfunction "PC7(ICP1/INT4/CLKO)_22") (pintype "bidirectional"))
    )
    (net (code "84") (name "unconnected-(IC1-PD2(INT2{slash}AIN1{slash}RXD1)-Pad8)") (class "Default")
      (node (ref "IC1") (pin "8") (pinfunction "PD2(INT2/AIN1/RXD1)_8") (pintype "bidirectional"))
    )
    (net (code "85") (name "unconnected-(IC1-PD3(INT3{slash}TXD1)-Pad9)") (class "Default")
      (node (ref "IC1") (pin "9") (pinfunction "PD3(INT3/TXD1)_9") (pintype "bidirectional"))
    )
    (net (code "86") (name "unconnected-(IC1-PD4(INT5{slash}AIN3)-Pad10)") (class "Default")
      (node (ref "IC1") (pin "10") (pinfunction "PD4(INT5/AIN3)_10") (pintype "bidirectional"))
    )
    (net (code "87") (name "unconnected-(IC1-PD5(XCK{slash}AIN4{slash}PCINT12)-Pad11)") (class "Default")
      (node (ref "IC1") (pin "11") (pinfunction "PD5(XCK/AIN4/PCINT12)_11") (pintype "bidirectional"))
    )
    (net (code "88") (name "unconnected-(IC1-PD6(INT6{slash}AIN5{slash}RTS)-Pad12)") (class "Default")
      (node (ref "IC1") (pin "12") (pinfunction "PD6(INT6/AIN5/RTS)_12") (pintype "bidirectional"))
    )
    (net (code "89") (name "unconnected-(IC1-PD7(INT7{slash}HWB{slash}AIN6{slash}T0)-Pad13)") (class "Default")
      (node (ref "IC1") (pin "13") (pinfunction "PD7(INT7/HWB/AIN6/T0)_13") (pintype "bidirectional"))
    )
    (net (code "90") (name "unconnected-(J1-SBU1-PadA8)") (class "Default")
      (node (ref "J1") (pin "A8") (pinfunction "SBU1_A8") (pintype "bidirectional"))
    )
    (net (code "91") (name "unconnected-(J1-SBU2-PadB8)") (class "Default")
      (node (ref "J1") (pin "B8") (pinfunction "SBU2_B8") (pintype "bidirectional"))
    )
    (net (code "92") (name "unconnected-(J1-SSRXN1-PadB10)") (class "Default")
      (node (ref "J1") (pin "B10") (pinfunction "SSRXN1_B10") (pintype "bidirectional"))
    )
    (net (code "93") (name "unconnected-(J1-SSRXN2-PadA10)") (class "Default")
      (node (ref "J1") (pin "A10") (pinfunction "SSRXN2_A10") (pintype "bidirectional"))
    )
    (net (code "94") (name "unconnected-(J1-SSRXP1-PadB11)") (class "Default")
      (node (ref "J1") (pin "B11") (pinfunction "SSRXP1_B11") (pintype "bidirectional"))
    )
    (net (code "95") (name "unconnected-(J1-SSRXP2-PadA11)") (class "Default")
      (node (ref "J1") (pin "A11") (pinfunction "SSRXP2_A11") (pintype "bidirectional"))
    )
    (net (code "96") (name "unconnected-(J1-SSTXN1-PadA3)") (class "Default")
      (node (ref "J1") (pin "A3") (pinfunction "SSTXN1_A3") (pintype "bidirectional"))
    )
    (net (code "97") (name "unconnected-(J1-SSTXN2-PadB3)") (class "Default")
      (node (ref "J1") (pin "B3") (pinfunction "SSTXN2_B3") (pintype "bidirectional"))
    )
    (net (code "98") (name "unconnected-(J1-SSTXP1-PadA2)") (class "Default")
      (node (ref "J1") (pin "A2") (pinfunction "SSTXP1_A2") (pintype "bidirectional"))
    )
    (net (code "99") (name "unconnected-(J1-SSTXP2-PadB2)") (class "Default")
      (node (ref "J1") (pin "B2") (pinfunction "SSTXP2_B2") (pintype "bidirectional"))
    )
    (net (code "100") (name "unconnected-(S3-PadO)") (class "Default")
      (node (ref "S3") (pin "O") (pinfunction "O_O") (pintype "passive"))
    )
    (net (code "101") (name "unconnected-(U1-ORIENT-Pad8)") (class "Default")
      (node (ref "U1") (pin "8") (pinfunction "ORIENT_8") (pintype "passive"))
    )
    (net (code "102") (name "unconnected-(U1-SWMONI-Pad9)") (class "Default")
      (node (ref "U1") (pin "9") (pinfunction "SWMONI_9") (pintype "output"))
    )
  )
)
